# SCH_NFC-Card-Athish_2024-10-27_1.net
KiCad netlist of a schematic drawn in EasyEDA
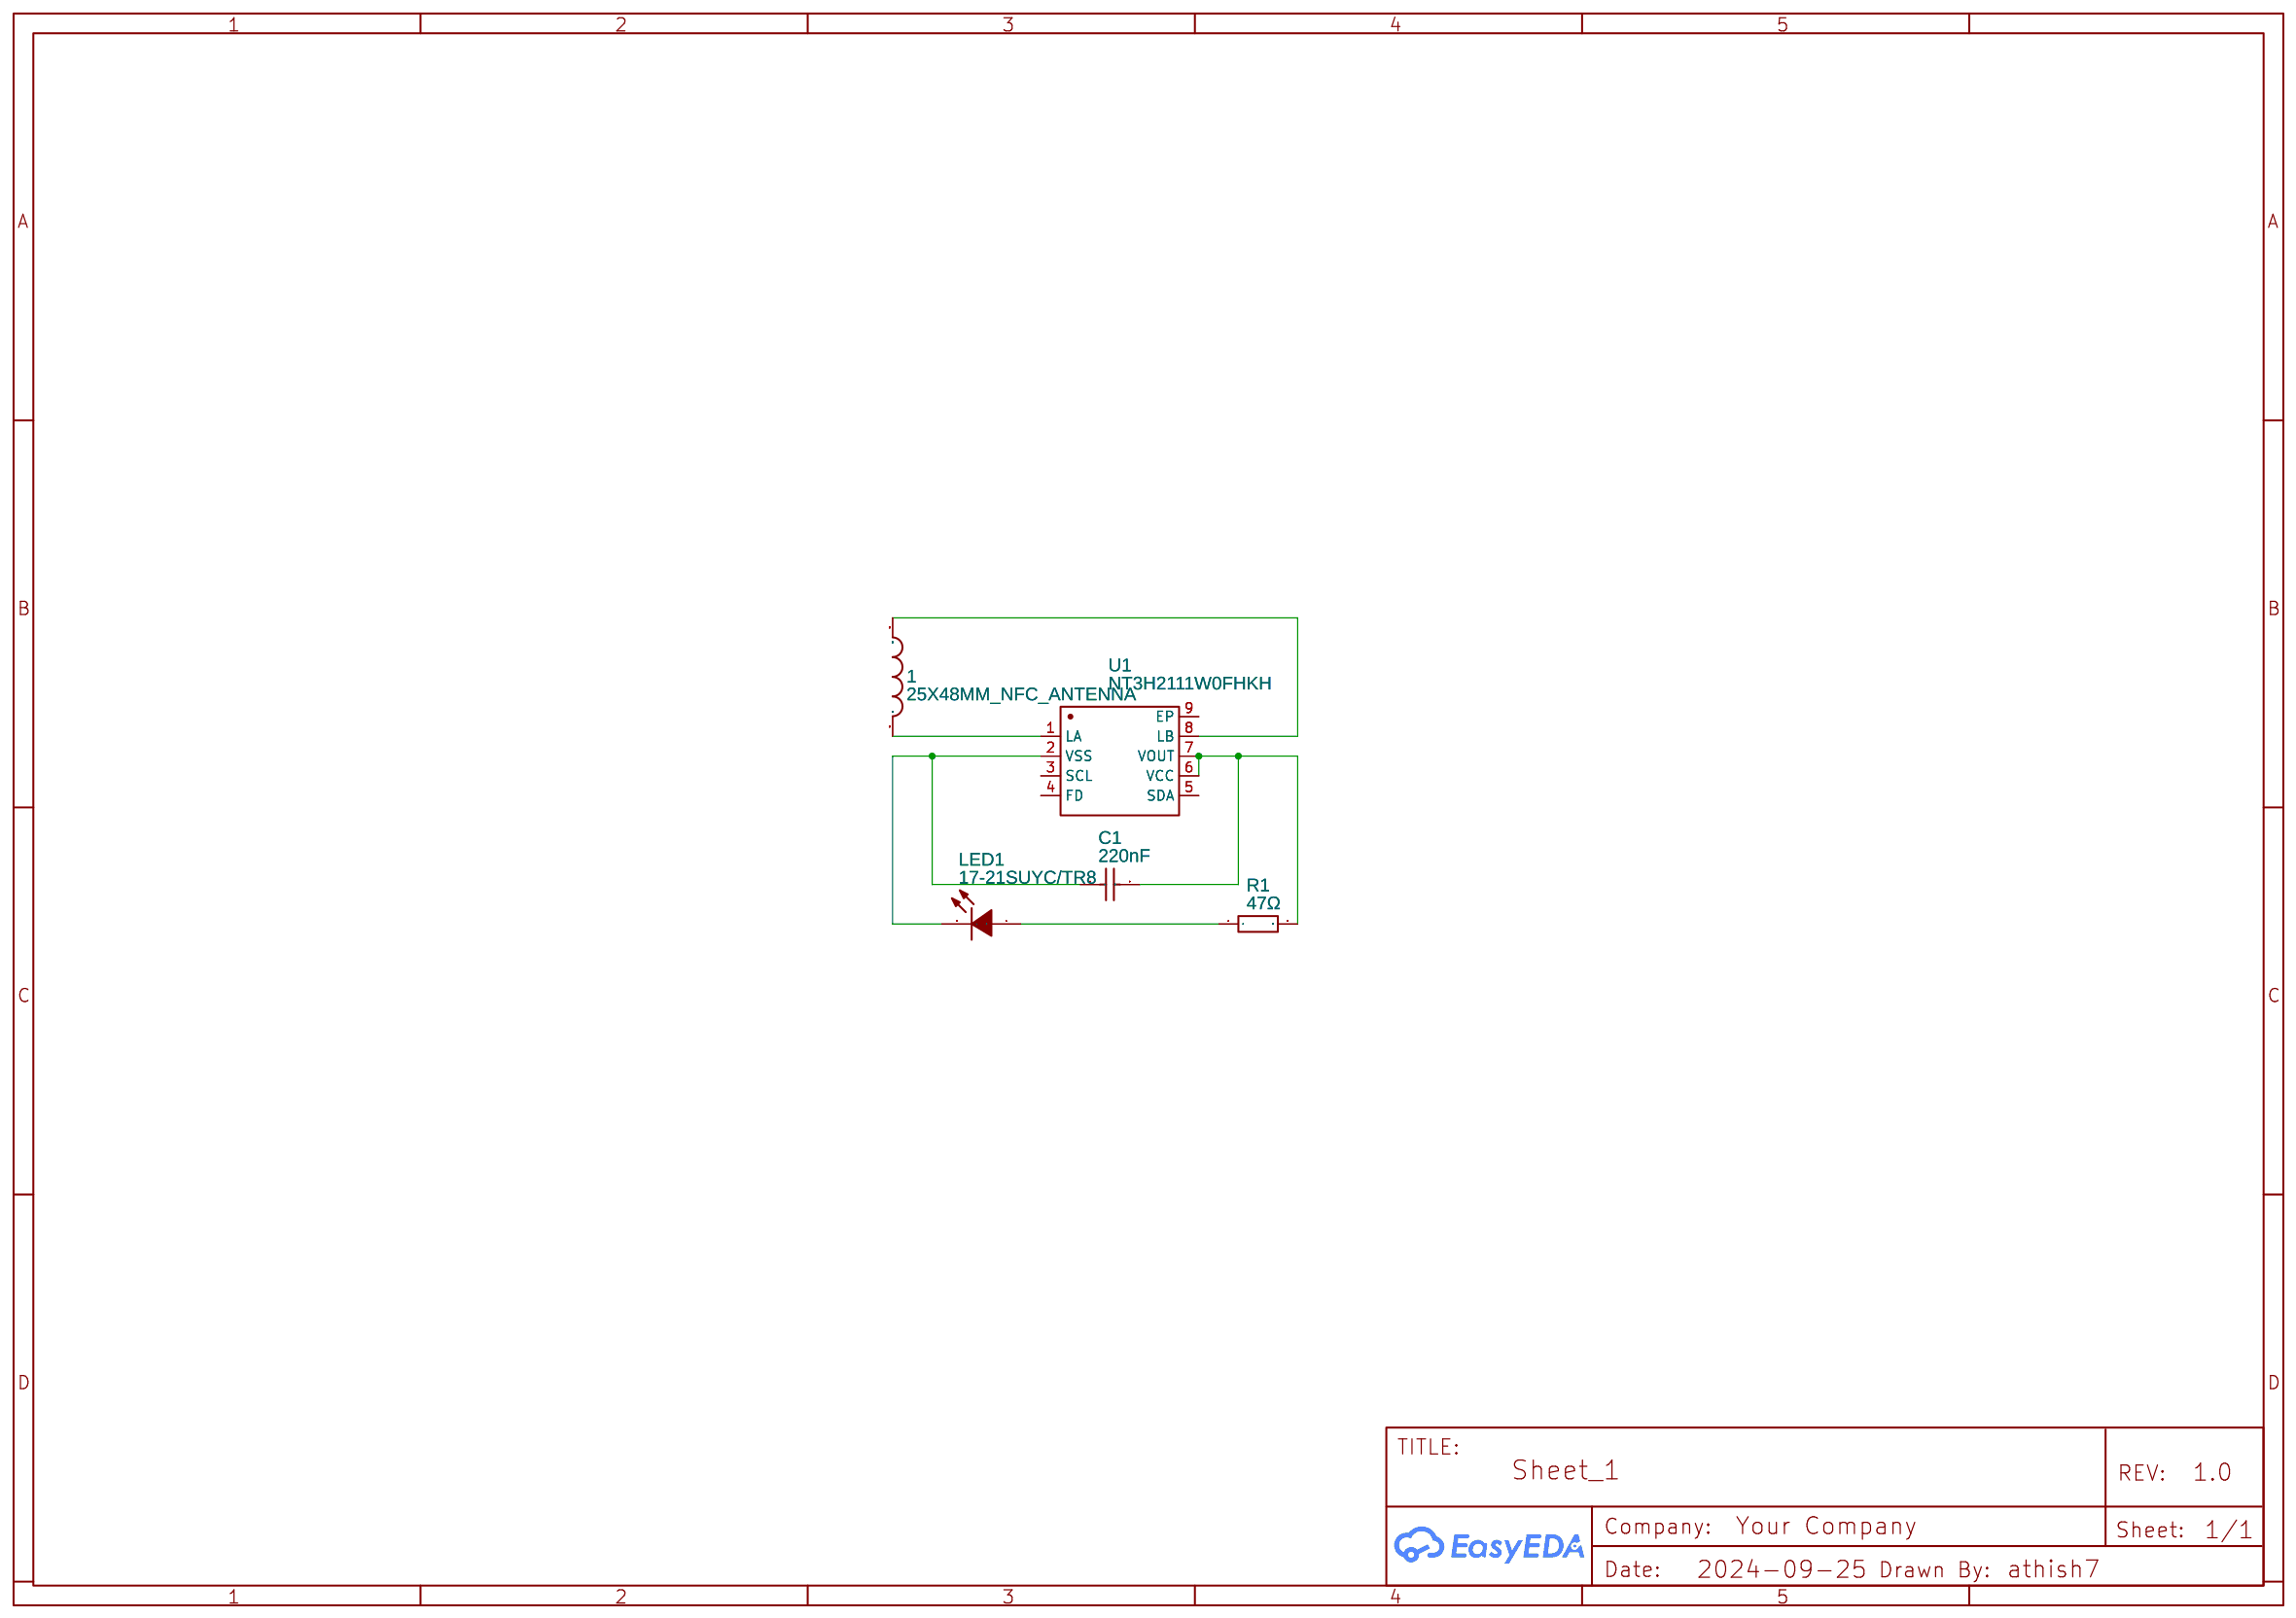
[diagram p0: schematic sheet]

(export (version "E")
  (design (tool "Eeschema 10.0.6"))
  (components
    (comp (ref "1") (value "25X48MM_NFC_ANTENNA") (libsource (lib "") (part "25X48MM_NFC_ANTENNA")))
    (comp (ref "C1")
      (value "220nF")
      (fields
        (field (name "Manufacturer Part") "CL10B224KA8NNNC")
        (field (name "Manufacturer") "SAMSUNG(三星)")
      )
      (libsource (lib "") (part "CL10B224KA8NNNC"))
    )
    (comp (ref "LED1")
      (value "17-21SUYC/TR8")
      (fields (field (name "Manufacturer Part") "KT-0805黄灯") (field (name "Manufacturer") "KENTO"))
      (libsource (lib "") (part "17-21SUYC/TR8"))
    )
    (comp (ref "R1")
      (value "47Ω")
      (fields
        (field (name "Manufacturer Part") "0603WAF470JT5E")
        (field (name "Manufacturer") "UNI-ROYAL(厚声)")
      )
      (libsource (lib "") (part "0603WAF470JT5E"))
    )
    (comp (ref "U1")
      (value "NT3H2111W0FHKH")
      (fields (field (name "Manufacturer") "NXP(恩智浦)"))
      (libsource (lib "") (part "NT3H2111W0FHKH"))
    )
  )
  (nets
    (net (code "1") (name "Net-(LED1-+)") (class "Default")
      (node (ref "LED1") (pin "1") (pinfunction "+_1") (pintype "unspecified"))
      (node (ref "R1") (pin "1") (pinfunction "1_1") (pintype "input"))
    )
    (net (code "2") (name "Net-(LED1--)") (class "Default")
      (node (ref "C1") (pin "1") (pinfunction "1_1") (pintype "input"))
      (node (ref "LED1") (pin "2") (pinfunction "-_2") (pintype "unspecified"))
      (node (ref "U1") (pin "2") (pinfunction "VSS_2") (pintype "unspecified"))
    )
    (net (code "3") (name "Net-(U1-LA)") (class "Default")
      (node (ref "1") (pin "P$2") (pinfunction "P$2_P$2") (pintype "bidirectional"))
      (node (ref "U1") (pin "1") (pinfunction "LA_1") (pintype "unspecified"))
    )
    (net (code "4") (name "Net-(U1-LB)") (class "Default")
      (node (ref "1") (pin "P$1") (pinfunction "P$1_P$1") (pintype "bidirectional"))
      (node (ref "U1") (pin "8") (pinfunction "LB_8") (pintype "unspecified"))
    )
    (net (code "5") (name "Net-(U1-VCC)") (class "Default")
      (node (ref "C1") (pin "2") (pinfunction "2_2") (pintype "input"))
      (node (ref "R1") (pin "2") (pinfunction "2_2") (pintype "input"))
      (node (ref "U1") (pin "6") (pinfunction "VCC_6") (pintype "unspecified"))
      (node (ref "U1") (pin "7") (pinfunction "VOUT_7") (pintype "unspecified"))
    )
    (net (code "6") (name "unconnected-(U1-EP-Pad9)") (class "Default")
      (node (ref "U1") (pin "9") (pinfunction "EP_9") (pintype "unspecified"))
    )
    (net (code "7") (name "unconnected-(U1-FD-Pad4)") (class "Default")
      (node (ref "U1") (pin "4") (pinfunction "FD_4") (pintype "unspecified"))
    )
    (net (code "8") (name "unconnected-(U1-SCL-Pad3)") (class "Default")
      (node (ref "U1") (pin "3") (pinfunction "SCL_3") (pintype "unspecified"))
    )
    (net (code "9") (name "unconnected-(U1-SDA-Pad5)") (class "Default")
      (node (ref "U1") (pin "5") (pinfunction "SDA_5") (pintype "unspecified"))
    )
  )
)
